# Power.net
KiCad netlist of a schematic drawn in Altium Designer
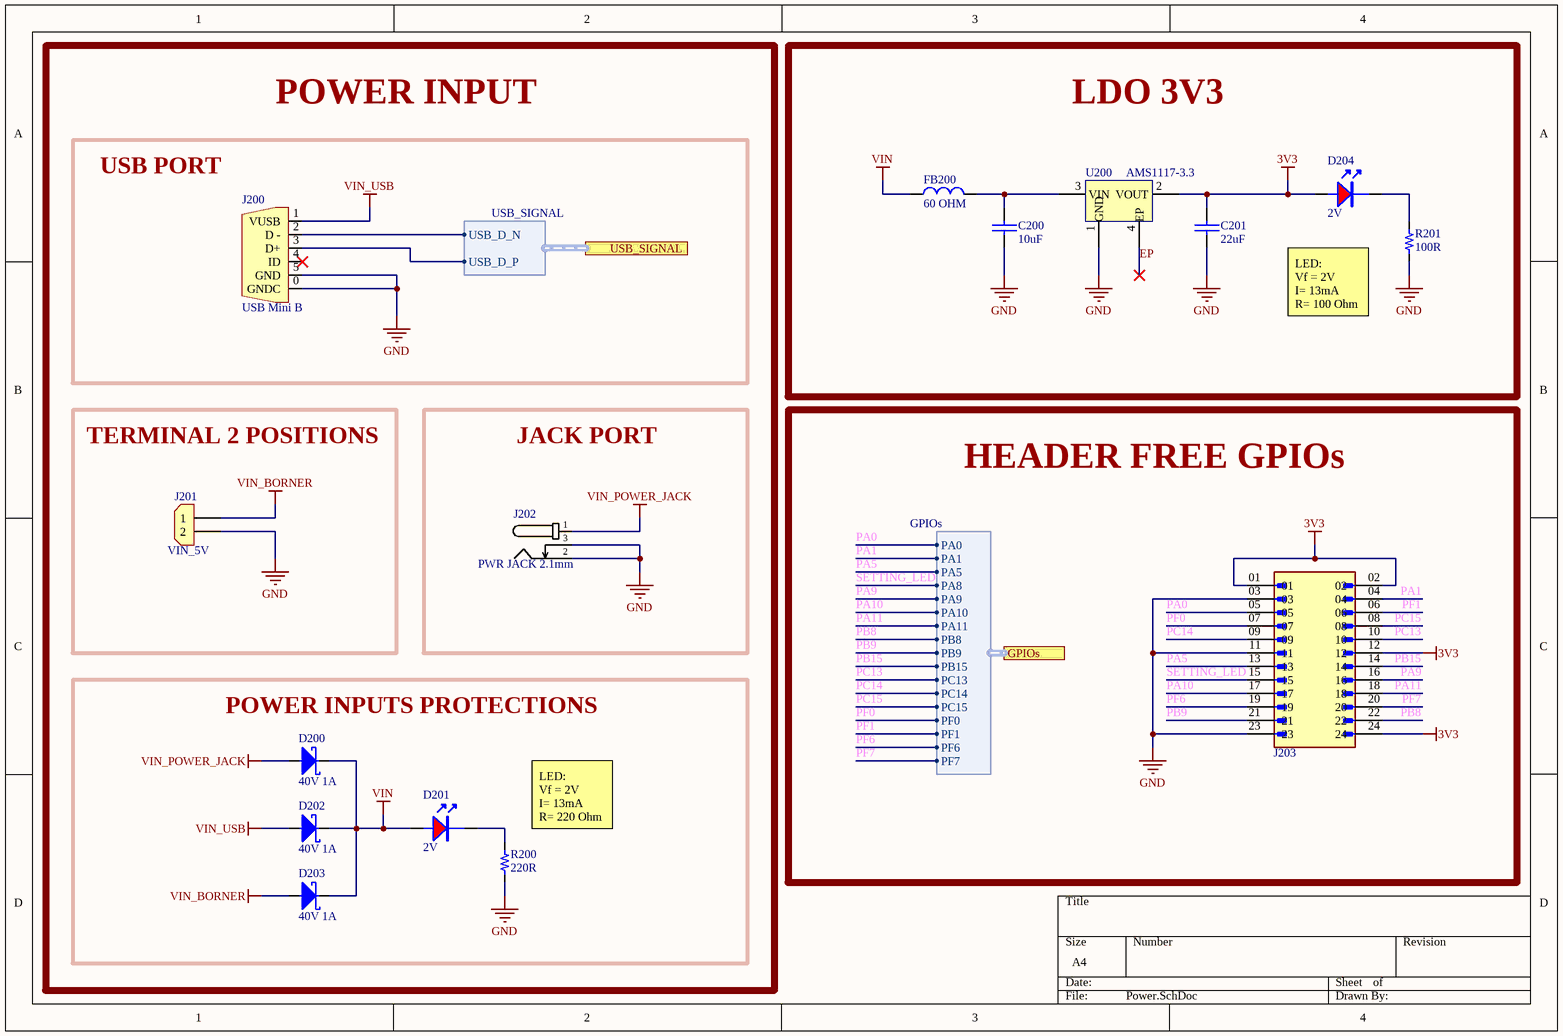
[diagram p0: Power.SchDoc]

(export (version "E")
  (design (tool "Eeschema 10.0.6"))
  (components
    (comp (ref "C200")
      (value "10uF")
      (footprint "0603_cap")
      (description "10V 10uF X5R ±10% 0603 Multilayer Ceramic Capacitors MLCC - SMD/SMT ROHS")
      (fields
        (field (name "MANUFACTURER") "CCTC")
        (field (name "MANUFACTURER PART NUMBER") "TCC0603X5R106K100CT")
      )
      (libsource (lib "shared_lib") (part "Cap_10uF_0603_10V"))
    )
    (comp (ref "C201")
      (value "22uF")
      (footprint "0603_cap")
      (description "6.3V 22uF X5R ±20% 0805 Multilayer Ceramic Capacitors MLCC - SMD/SMT ROHS")
      (fields
        (field (name "MANUFACTURER") "Samsung Electro-Mechanics")
        (field (name "MANUFACTURER PART NUMBER") "CL21A226MQQNNNE")
      )
      (libsource (lib "shared_lib") (part "Cap_22uF_0805_6V3"))
    )
    (comp (ref "D200")
      (value "40V 1A")
      (footprint "SOD_123")
      (description "DIODE SCHOTTKY 40V 1A SOD123F")
      (fields
        (field (name "MANUFACTURER") "Shanghai Prisemi Elec")
        (field (name "MANUFACTURER PART NUMBER") "PSBD1DF40V1H")
      )
      (libsource (lib "shared_lib") (part "D_Schottky_40V_1A_SOD_123F"))
    )
    (comp (ref "D201")
      (value "2V")
      (footprint "0805_LED")
      (description "LED RED CLEAR 0805 SMD")
      (fields
        (field (name "MANUFACTURER") "XINGLIGHT")
        (field (name "MANUFACTURER PART NUMBER") "XL-2012SURC")
      )
      (libsource (lib "shared_lib") (part "LED_0805_RED"))
    )
    (comp (ref "D202")
      (value "40V 1A")
      (footprint "SOD_123")
      (description "DIODE SCHOTTKY 40V 1A SOD123F")
      (fields
        (field (name "MANUFACTURER") "Shanghai Prisemi Elec")
        (field (name "MANUFACTURER PART NUMBER") "PSBD1DF40V1H")
      )
      (libsource (lib "shared_lib") (part "D_Schottky_40V_1A_SOD_123F"))
    )
    (comp (ref "D203")
      (value "40V 1A")
      (footprint "SOD_123")
      (description "DIODE SCHOTTKY 40V 1A SOD123F")
      (fields
        (field (name "MANUFACTURER") "Shanghai Prisemi Elec")
        (field (name "MANUFACTURER PART NUMBER") "PSBD1DF40V1H")
      )
      (libsource (lib "shared_lib") (part "D_Schottky_40V_1A_SOD_123F"))
    )
    (comp (ref "D204")
      (value "2V")
      (footprint "0805_LED")
      (description "LED RED CLEAR 0805 SMD")
      (fields
        (field (name "MANUFACTURER") "XINGLIGHT")
        (field (name "MANUFACTURER PART NUMBER") "XL-2012SURC")
      )
      (libsource (lib "shared_lib") (part "LED_0805_RED"))
    )
    (comp (ref "FB200")
      (value "60 OHM")
      (footprint "0603_fb")
      (description "2A 1 100mΩ 60Ω@100MHz ±25% 0603 Ferrite Beads ROHS")
      (fields
        (field (name "MANUFACTURER") "TAI-TECH")
        (field (name "MANUFACTURER PART NUMBER") "HCB1608KF-600T20")
      )
      (libsource (lib "shared_lib") (part "FB_60_0603_2A"))
    )
    (comp (ref "J200")
      (value "USB Mini B")
      (footprint "CON_5x1_SMD_miniUSB_B")
      (description "CONN RCPT USB2.0 MINI B SMD R/A")
      (fields
        (field (name "MANUFACTURER PART NUMBER") "KH-MINI-SMT-5P-Cu")
        (field (name "MANUFACTURER") "EDAC Inc.")
      )
      (libsource (lib "shared_lib") (part "Con_Mini_USB_B"))
    )
    (comp (ref "J201")
      (value "VIN_5V")
      (footprint "CON_2x1_TH_5MM")
      (description "2POS 5MM")
      (fields (field (name "MANUFACTURER") "JILN") (field (name "MANUFACTURER PART NUMBER") "JL126-50002G01"))
      (libsource (lib "shared_lib") (part "Con_2x1_TH_5mm"))
    )
    (comp (ref "J202")
      (value "PWR JACK 2.1mm")
      (footprint "CON_POWER_BARREL_2.1MM_3CONN")
      (description "CONN PWR JACK 2X5.5MM SOLDER")
      (fields (field (name "MANUFACTURER") "HCTL") (field (name "MANUFACTURER PART NUMBER") "HC-DC-005-2.0T"))
      (libsource (lib "shared_lib") (part "Con_Power_Jack_2.1mm_3pins"))
    )
    (comp (ref "J203")
      (value "10129381-924001BLF")
      (footprint "CON_2x12_th_2.54MM")
      (description "CONN HEADER VERT 24POS 2.54MM")
      (fields (field (name "MANUFACTURER") "Amphenol ICC (FCI)"))
      (libsource (lib "Bicycle_project") (part "Con_2x12_TH_2.54mm"))
    )
    (comp (ref "R200")
      (value "220R")
      (footprint "0603_res")
      (description "RES SMD 220R OHM 5% 1/10W 0603")
      (fields
        (field (name "MANUFACTURER") "FOJAN")
        (field (name "MANUFACTURER PART NUMBER") "FRC0603J221 TS")
      )
      (libsource (lib "shared_lib") (part "Res_220R_0603_1/10W"))
    )
    (comp (ref "R201")
      (value "100R")
      (footprint "0603_res")
      (description "RES SMD 100R OHM 5% 1/10W 0603")
      (fields
        (field (name "MANUFACTURER") "FOJAN")
        (field (name "MANUFACTURER PART NUMBER") "FRC0603J101 TS")
      )
      (libsource (lib "shared_lib") (part "Res_100R_0603_1/10W"))
    )
    (comp (ref "U200")
      (value "AMS1117-3.3")
      (footprint "SOT_223")
      (description "1A 60dB@(120Hz) Fixed 3.3V Positive 18V SOT-223 Linear Voltage Regulators (LDO) ROHS")
      (fields (field (name "MANUFACTURER") "UMW(Youtai Semiconductor Co., Ltd.)"))
      (libsource (lib "shared_lib") (part "LDO_3V3_1A_FIXED"))
    )
  )
  (nets
    (net (code "3") (name "/EP") (class "Default")
      (node (ref "U200") (pin "4") (pinfunction "EP_4") (pintype "passive+no_connect"))
    )
    (net (code "4") (name "/PA0") (class "Default")
      (node (ref "J203") (pin "05") (pinfunction "05_05") (pintype "passive"))
    )
    (net (code "5") (name "/PA1") (class "Default")
      (node (ref "J203") (pin "04") (pinfunction "04_04") (pintype "passive"))
    )
    (net (code "6") (name "/PA5") (class "Default")
      (node (ref "J203") (pin "13") (pinfunction "13_13") (pintype "passive"))
    )
    (net (code "7") (name "/PA9") (class "Default")
      (node (ref "J203") (pin "16") (pinfunction "16_16") (pintype "passive"))
    )
    (net (code "8") (name "/PA10") (class "Default")
      (node (ref "J203") (pin "17") (pinfunction "17_17") (pintype "passive"))
    )
    (net (code "9") (name "/PA11") (class "Default")
      (node (ref "J203") (pin "18") (pinfunction "18_18") (pintype "passive"))
    )
    (net (code "10") (name "/PB8") (class "Default")
      (node (ref "J203") (pin "22") (pinfunction "22_22") (pintype "passive"))
    )
    (net (code "11") (name "/PB9") (class "Default")
      (node (ref "J203") (pin "21") (pinfunction "21_21") (pintype "passive"))
    )
    (net (code "12") (name "/PB15") (class "Default")
      (node (ref "J203") (pin "14") (pinfunction "14_14") (pintype "passive"))
    )
    (net (code "13") (name "/PC13") (class "Default")
      (node (ref "J203") (pin "10") (pinfunction "10_10") (pintype "passive"))
    )
    (net (code "14") (name "/PC14") (class "Default")
      (node (ref "J203") (pin "09") (pinfunction "09_09") (pintype "passive"))
    )
    (net (code "15") (name "/PC15") (class "Default")
      (node (ref "J203") (pin "08") (pinfunction "08_08") (pintype "passive"))
    )
    (net (code "16") (name "/PF0") (class "Default")
      (node (ref "J203") (pin "07") (pinfunction "07_07") (pintype "passive"))
    )
    (net (code "17") (name "/PF1") (class "Default")
      (node (ref "J203") (pin "06") (pinfunction "06_06") (pintype "passive"))
    )
    (net (code "18") (name "/PF6") (class "Default")
      (node (ref "J203") (pin "19") (pinfunction "19_19") (pintype "passive"))
    )
    (net (code "19") (name "/PF7") (class "Default")
      (node (ref "J203") (pin "20") (pinfunction "20_20") (pintype "passive"))
    )
    (net (code "20") (name "/SETTING_LED") (class "Default")
      (node (ref "J203") (pin "15") (pinfunction "15_15") (pintype "passive"))
    )
    (net (code "21") (name "/USB_D_N") (class "Default")
      (node (ref "J200") (pin "2") (pinfunction "D_-_2") (pintype "passive"))
    )
    (net (code "22") (name "/USB_D_P") (class "Default")
      (node (ref "J200") (pin "3") (pinfunction "D+_3") (pintype "passive"))
    )
    (net (code "25") (name "3V3") (class "Default")
      (node (ref "C201") (pin "1") (pinfunction "1_1") (pintype "passive"))
      (node (ref "D204") (pin "1") (pinfunction "A_1") (pintype "passive"))
      (node (ref "J203") (pin "01") (pinfunction "01_01") (pintype "passive"))
      (node (ref "J203") (pin "02") (pinfunction "02_02") (pintype "passive"))
      (node (ref "J203") (pin "12") (pinfunction "12_12") (pintype "passive"))
      (node (ref "J203") (pin "24") (pinfunction "24_24") (pintype "passive"))
      (node (ref "U200") (pin "2") (pinfunction "VOUT_2") (pintype "passive"))
    )
    (net (code "26") (name "GND") (class "Default")
      (node (ref "C200") (pin "2") (pinfunction "2_2") (pintype "passive"))
      (node (ref "C201") (pin "2") (pinfunction "2_2") (pintype "passive"))
      (node (ref "J200") (pin "0") (pinfunction "GNDC_0") (pintype "passive"))
      (node (ref "J200") (pin "5") (pinfunction "GND_5") (pintype "passive"))
      (node (ref "J201") (pin "2") (pinfunction "2_2") (pintype "passive"))
      (node (ref "J202") (pin "2") (pinfunction "2_2") (pintype "passive"))
      (node (ref "J202") (pin "3") (pinfunction "3_3") (pintype "passive"))
      (node (ref "J203") (pin "03") (pinfunction "03_03") (pintype "passive"))
      (node (ref "J203") (pin "11") (pinfunction "11_11") (pintype "passive"))
      (node (ref "J203") (pin "23") (pinfunction "23_23") (pintype "passive"))
      (node (ref "R200") (pin "1") (pinfunction "1_1") (pintype "passive"))
      (node (ref "R201") (pin "1") (pinfunction "1_1") (pintype "passive"))
      (node (ref "U200") (pin "1") (pinfunction "GND_1") (pintype "passive"))
    )
    (net (code "27") (name "Net-(D201-Pad2)") (class "Default")
      (node (ref "D201") (pin "2") (pinfunction "2_2") (pintype "passive"))
      (node (ref "R200") (pin "2") (pinfunction "2_2") (pintype "passive"))
    )
    (net (code "28") (name "Net-(D204-Pad2)") (class "Default")
      (node (ref "D204") (pin "2") (pinfunction "2_2") (pintype "passive"))
      (node (ref "R201") (pin "2") (pinfunction "2_2") (pintype "passive"))
    )
    (net (code "29") (name "Net-(U200-VIN)") (class "Default")
      (node (ref "C200") (pin "1") (pinfunction "1_1") (pintype "passive"))
      (node (ref "FB200") (pin "2") (pinfunction "2_2") (pintype "passive"))
      (node (ref "U200") (pin "3") (pinfunction "VIN_3") (pintype "passive"))
    )
    (net (code "30") (name "VIN") (class "Default")
      (node (ref "D200") (pin "1") (pinfunction "1_1") (pintype "passive"))
      (node (ref "D201") (pin "1") (pinfunction "A_1") (pintype "passive"))
      (node (ref "D202") (pin "1") (pinfunction "1_1") (pintype "passive"))
      (node (ref "D203") (pin "1") (pinfunction "1_1") (pintype "passive"))
      (node (ref "FB200") (pin "1") (pinfunction "1_1") (pintype "passive"))
    )
    (net (code "31") (name "VIN_BORNER") (class "Default")
      (node (ref "D203") (pin "2") (pinfunction "2_2") (pintype "passive"))
      (node (ref "J201") (pin "1") (pinfunction "1_1") (pintype "passive"))
    )
    (net (code "32") (name "VIN_POWER_JACK") (class "Default")
      (node (ref "D200") (pin "2") (pinfunction "2_2") (pintype "passive"))
      (node (ref "J202") (pin "1") (pinfunction "1_1") (pintype "passive"))
    )
    (net (code "33") (name "VIN_USB") (class "Default")
      (node (ref "D202") (pin "2") (pinfunction "2_2") (pintype "passive"))
      (node (ref "J200") (pin "1") (pinfunction "VUSB_1") (pintype "passive"))
    )
    (net (code "34") (name "unconnected-(J200-ID-Pad4)") (class "Default")
      (node (ref "J200") (pin "4") (pinfunction "ID_4") (pintype "passive+no_connect"))
    )
  )
)
